# 8channelsULN2803.net
KiCad netlist of a schematic drawn in EAGLE
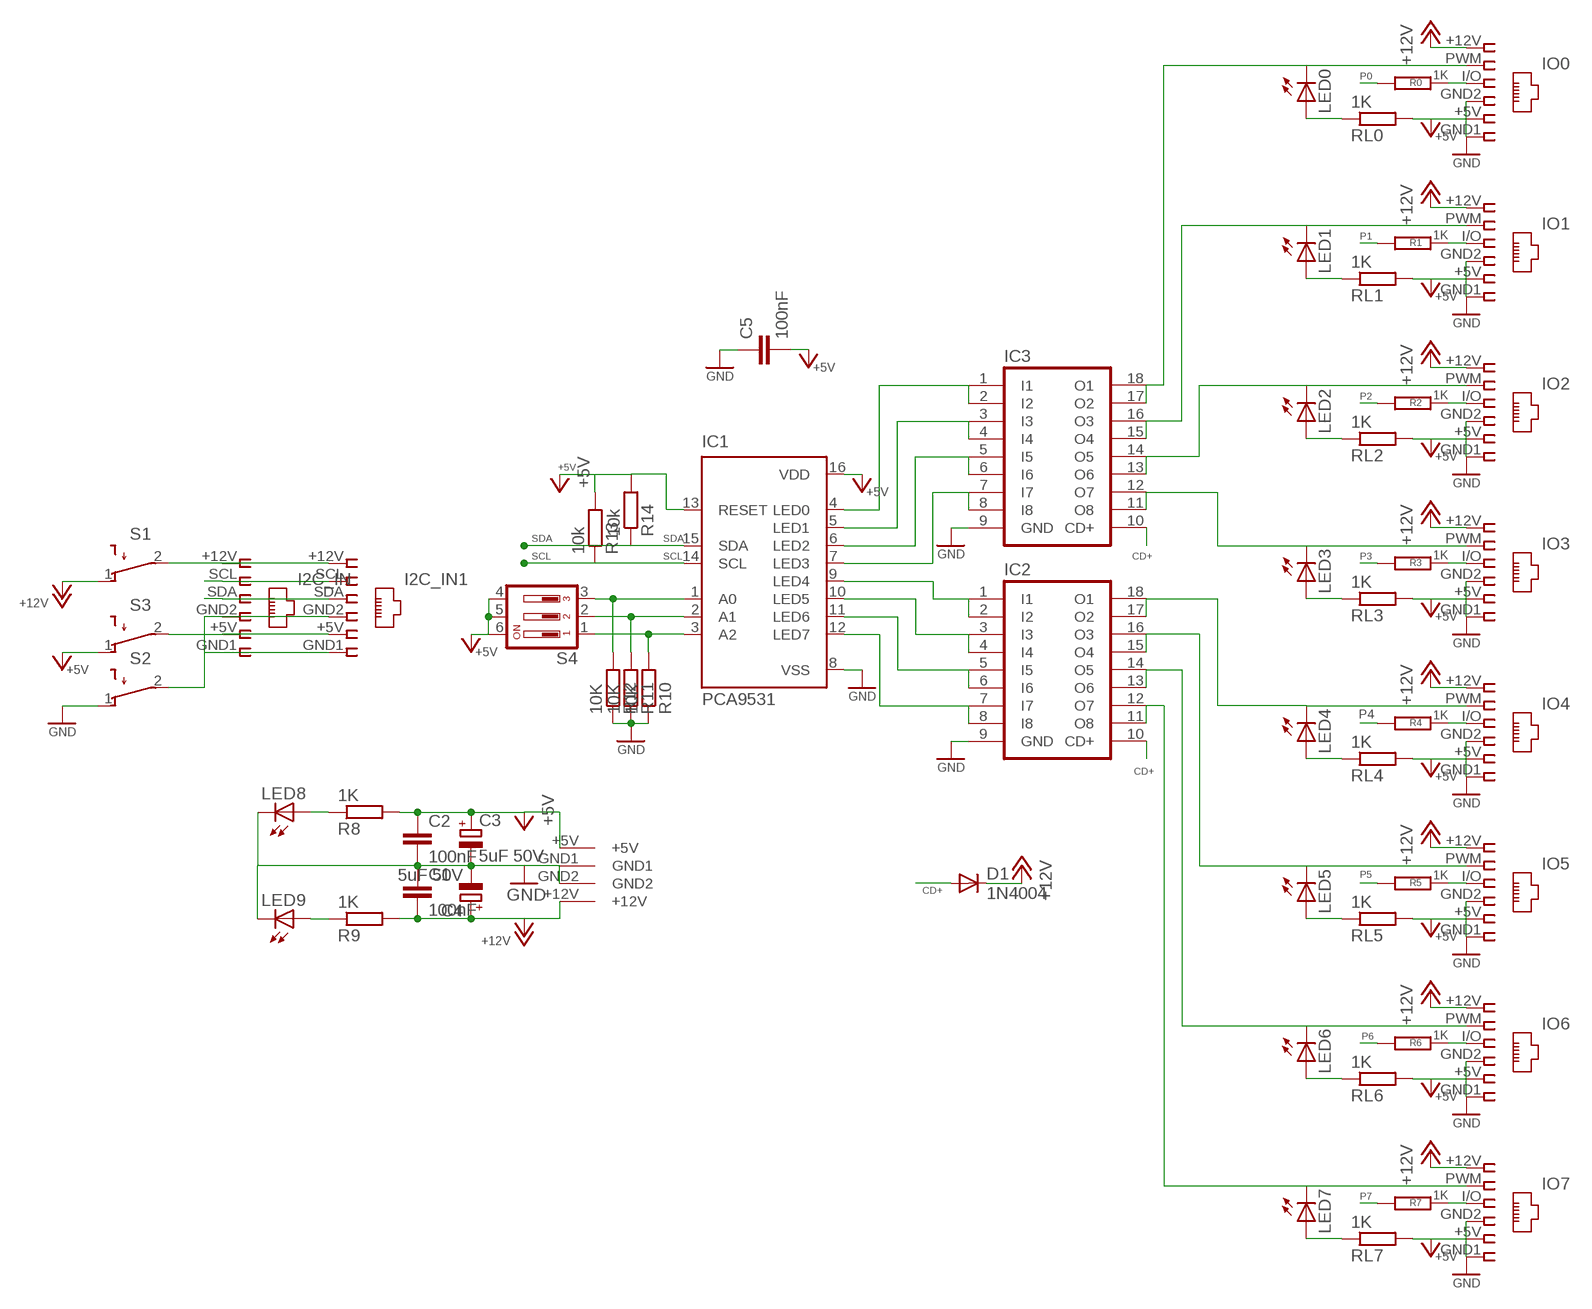
[diagram p0: schematic, sheet 1]

(export (version "E")
  (design (tool "Eeschema 10.0.6"))
  (components
    (comp (ref "C1")
      (value "100nF")
      (footprint "eagle-import:C1206")
      (libsource (lib "eagle-import") (part "C-EUC1206"))
    )
    (comp (ref "C2")
      (value "100nF")
      (footprint "eagle-import:C1206")
      (libsource (lib "eagle-import") (part "C-EUC1206"))
    )
    (comp (ref "C3")
      (value "5uF 50V")
      (footprint "eagle-import:E3,5-8")
      (libsource (lib "eagle-import") (part "CPOL-EUE3.5-8"))
    )
    (comp (ref "C4")
      (value "5uF 50V")
      (footprint "eagle-import:E3,5-8")
      (libsource (lib "eagle-import") (part "CPOL-EUE3.5-8"))
    )
    (comp (ref "C5")
      (value "100nF")
      (footprint "eagle-import:C1206")
      (libsource (lib "eagle-import") (part "C-EUC1206"))
    )
    (comp (ref "D1")
      (value "1N4004")
      (footprint "eagle-import:DO41-10")
      (libsource (lib "eagle-import") (part "1N4004"))
    )
    (comp (ref "I2C_IN")
      (value "I2C 1")
      (footprint "eagle-import:RJ12-STRAIGHT-I2C")
      (libsource (lib "eagle-import") (part "RJ12STRAIGHT-I2C"))
    )
    (comp (ref "I2C_IN1")
      (value "I2C 2")
      (footprint "eagle-import:RJ12-STRAIGHT-I2C")
      (libsource (lib "eagle-import") (part "RJ12STRAIGHT-I2C"))
    )
    (comp (ref "IC1")
      (value "PCA9531")
      (footprint "eagle-import:SO16")
      (libsource (lib "eagle-import") (part "PCA9531"))
    )
    (comp (ref "IC2")
      (value "ULN2803A")
      (footprint "eagle-import:DIL18")
      (libsource (lib "eagle-import") (part "ULN2803A"))
    )
    (comp (ref "IC3")
      (value "ULN2803A")
      (footprint "eagle-import:DIL18")
      (libsource (lib "eagle-import") (part "ULN2803A"))
    )
    (comp (ref "IO0")
      (value "IO0")
      (footprint "eagle-import:RJ12-STRAIGHT")
      (libsource (lib "eagle-import") (part "RJ12STRAIGHT"))
    )
    (comp (ref "IO1")
      (value "IO1")
      (footprint "eagle-import:RJ12-STRAIGHT")
      (libsource (lib "eagle-import") (part "RJ12STRAIGHT"))
    )
    (comp (ref "IO2")
      (value "IO2")
      (footprint "eagle-import:RJ12-STRAIGHT")
      (libsource (lib "eagle-import") (part "RJ12STRAIGHT"))
    )
    (comp (ref "IO3")
      (value "IO3")
      (footprint "eagle-import:RJ12-STRAIGHT")
      (libsource (lib "eagle-import") (part "RJ12STRAIGHT"))
    )
    (comp (ref "IO4")
      (value "IO4")
      (footprint "eagle-import:RJ12-STRAIGHT")
      (libsource (lib "eagle-import") (part "RJ12STRAIGHT"))
    )
    (comp (ref "IO5")
      (value "IO5")
      (footprint "eagle-import:RJ12-STRAIGHT")
      (libsource (lib "eagle-import") (part "RJ12STRAIGHT"))
    )
    (comp (ref "IO6")
      (value "IO6")
      (footprint "eagle-import:RJ12-STRAIGHT")
      (libsource (lib "eagle-import") (part "RJ12STRAIGHT"))
    )
    (comp (ref "IO7")
      (value "IO7")
      (footprint "eagle-import:RJ12-STRAIGHT")
      (libsource (lib "eagle-import") (part "RJ12STRAIGHT"))
    )
    (comp (ref "LED0")
      (value "LED3MM")
      (footprint "eagle-import:LED3MM")
      (libsource (lib "eagle-import") (part "LED3MM"))
    )
    (comp (ref "LED1")
      (value "LED3MM")
      (footprint "eagle-import:LED3MM")
      (libsource (lib "eagle-import") (part "LED3MM"))
    )
    (comp (ref "LED2")
      (value "LED3MM")
      (footprint "eagle-import:LED3MM")
      (libsource (lib "eagle-import") (part "LED3MM"))
    )
    (comp (ref "LED3")
      (value "LED3MM")
      (footprint "eagle-import:LED3MM")
      (libsource (lib "eagle-import") (part "LED3MM"))
    )
    (comp (ref "LED4")
      (value "LED3MM")
      (footprint "eagle-import:LED3MM")
      (libsource (lib "eagle-import") (part "LED3MM"))
    )
    (comp (ref "LED5")
      (value "LED3MM")
      (footprint "eagle-import:LED3MM")
      (libsource (lib "eagle-import") (part "LED3MM"))
    )
    (comp (ref "LED6")
      (value "LED3MM")
      (footprint "eagle-import:LED3MM")
      (libsource (lib "eagle-import") (part "LED3MM"))
    )
    (comp (ref "LED7")
      (value "LED3MM")
      (footprint "eagle-import:LED3MM")
      (libsource (lib "eagle-import") (part "LED3MM"))
    )
    (comp (ref "LED8")
      (value "LED3MM")
      (footprint "eagle-import:LED3MM")
      (libsource (lib "eagle-import") (part "LED3MM"))
    )
    (comp (ref "LED9")
      (value "LED3MM")
      (footprint "eagle-import:LED3MM")
      (libsource (lib "eagle-import") (part "LED3MM"))
    )
    (comp (ref "R0")
      (value "1K")
      (footprint "eagle-import:M1206")
      (libsource (lib "eagle-import") (part "R-EU_M1206"))
    )
    (comp (ref "R1")
      (value "1K")
      (footprint "eagle-import:M1206")
      (libsource (lib "eagle-import") (part "R-EU_M1206"))
    )
    (comp (ref "R2")
      (value "1K")
      (footprint "eagle-import:M1206")
      (libsource (lib "eagle-import") (part "R-EU_M1206"))
    )
    (comp (ref "R3")
      (value "1K")
      (footprint "eagle-import:M1206")
      (libsource (lib "eagle-import") (part "R-EU_M1206"))
    )
    (comp (ref "R4")
      (value "1K")
      (footprint "eagle-import:M1206")
      (libsource (lib "eagle-import") (part "R-EU_M1206"))
    )
    (comp (ref "R5")
      (value "1K")
      (footprint "eagle-import:M1206")
      (libsource (lib "eagle-import") (part "R-EU_M1206"))
    )
    (comp (ref "R6")
      (value "1K")
      (footprint "eagle-import:M1206")
      (libsource (lib "eagle-import") (part "R-EU_M1206"))
    )
    (comp (ref "R7")
      (value "1K")
      (footprint "eagle-import:M1206")
      (libsource (lib "eagle-import") (part "R-EU_M1206"))
    )
    (comp (ref "R8")
      (value "1K")
      (footprint "eagle-import:M1206")
      (libsource (lib "eagle-import") (part "R-EU_M1206"))
    )
    (comp (ref "R9")
      (value "1K")
      (footprint "eagle-import:M1206")
      (libsource (lib "eagle-import") (part "R-EU_M1206"))
    )
    (comp (ref "R10")
      (value "10K")
      (footprint "eagle-import:M1206")
      (libsource (lib "eagle-import") (part "R-EU_M1206"))
    )
    (comp (ref "R11")
      (value "10K")
      (footprint "eagle-import:M1206")
      (libsource (lib "eagle-import") (part "R-EU_M1206"))
    )
    (comp (ref "R12")
      (value "10K")
      (footprint "eagle-import:M1206")
      (libsource (lib "eagle-import") (part "R-EU_M1206"))
    )
    (comp (ref "R13")
      (value "10k")
      (footprint "eagle-import:M1206")
      (libsource (lib "eagle-import") (part "R-EU_M1206"))
    )
    (comp (ref "R14")
      (value "10k")
      (footprint "eagle-import:M1206")
      (libsource (lib "eagle-import") (part "R-EU_M1206"))
    )
    (comp (ref "RL0")
      (value "1K")
      (footprint "eagle-import:M1206")
      (libsource (lib "eagle-import") (part "R-EU_M1206"))
    )
    (comp (ref "RL1")
      (value "1K")
      (footprint "eagle-import:M1206")
      (libsource (lib "eagle-import") (part "R-EU_M1206"))
    )
    (comp (ref "RL2")
      (value "1K")
      (footprint "eagle-import:M1206")
      (libsource (lib "eagle-import") (part "R-EU_M1206"))
    )
    (comp (ref "RL3")
      (value "1K")
      (footprint "eagle-import:M1206")
      (libsource (lib "eagle-import") (part "R-EU_M1206"))
    )
    (comp (ref "RL4")
      (value "1K")
      (footprint "eagle-import:M1206")
      (libsource (lib "eagle-import") (part "R-EU_M1206"))
    )
    (comp (ref "RL5")
      (value "1K")
      (footprint "eagle-import:M1206")
      (libsource (lib "eagle-import") (part "R-EU_M1206"))
    )
    (comp (ref "RL6")
      (value "1K")
      (footprint "eagle-import:M1206")
      (libsource (lib "eagle-import") (part "R-EU_M1206"))
    )
    (comp (ref "RL7")
      (value "1K")
      (footprint "eagle-import:M1206")
      (libsource (lib "eagle-import") (part "R-EU_M1206"))
    )
    (comp (ref "S1")
      (value "SWITCHSWITCH")
      (footprint "eagle-import:SWITCH2")
      (libsource (lib "eagle-import") (part "SWITCHSWITCH"))
    )
    (comp (ref "S2")
      (value "SWITCHPAD")
      (footprint "eagle-import:PADS2")
      (libsource (lib "eagle-import") (part "SWITCHPAD"))
    )
    (comp (ref "S3")
      (value "SWITCHSWITCH")
      (footprint "eagle-import:SWITCH2")
      (libsource (lib "eagle-import") (part "SWITCHSWITCH"))
    )
    (comp (ref "S4")
      (value "DIP03YL")
      (footprint "eagle-import:DIP03YL")
      (libsource (lib "eagle-import") (part "DIP03YL"))
    )
    (comp (ref "U$2")
      (value "KPJX-4S-S")
      (footprint "eagle-import:KPJX-4S-S")
      (libsource (lib "eagle-import") (part "KPJX-4S-S"))
    )
  )
  (nets
    (net (code "1") (name "+5V") (class "Default")
      (node (ref "C2") (pin "1") (pinfunction "1_1") (pintype "passive"))
      (node (ref "C3") (pin "+") (pinfunction "+_+") (pintype "passive"))
      (node (ref "C5") (pin "2") (pinfunction "2_2") (pintype "passive"))
      (node (ref "IC1") (pin "13") (pinfunction "RESET_13") (pintype "input"))
      (node (ref "IC1") (pin "16") (pinfunction "VDD_16") (pintype "power_in"))
      (node (ref "IO0") (pin "+5V") (pinfunction "5_+5V") (pintype "power_in"))
      (node (ref "IO1") (pin "+5V") (pinfunction "5_+5V") (pintype "power_in"))
      (node (ref "IO2") (pin "+5V") (pinfunction "5_+5V") (pintype "power_in"))
      (node (ref "IO3") (pin "+5V") (pinfunction "5_+5V") (pintype "power_in"))
      (node (ref "IO4") (pin "+5V") (pinfunction "5_+5V") (pintype "power_in"))
      (node (ref "IO5") (pin "+5V") (pinfunction "5_+5V") (pintype "power_in"))
      (node (ref "IO6") (pin "+5V") (pinfunction "5_+5V") (pintype "power_in"))
      (node (ref "IO7") (pin "+5V") (pinfunction "5_+5V") (pintype "power_in"))
      (node (ref "R13") (pin "2") (pinfunction "2_2") (pintype "passive"))
      (node (ref "R14") (pin "2") (pinfunction "2_2") (pintype "passive"))
      (node (ref "R8") (pin "2") (pinfunction "2_2") (pintype "passive"))
      (node (ref "RL0") (pin "2") (pinfunction "2_2") (pintype "passive"))
      (node (ref "RL1") (pin "2") (pinfunction "2_2") (pintype "passive"))
      (node (ref "RL2") (pin "2") (pinfunction "2_2") (pintype "passive"))
      (node (ref "RL3") (pin "2") (pinfunction "2_2") (pintype "passive"))
      (node (ref "RL4") (pin "2") (pinfunction "2_2") (pintype "passive"))
      (node (ref "RL5") (pin "2") (pinfunction "2_2") (pintype "passive"))
      (node (ref "RL6") (pin "2") (pinfunction "2_2") (pintype "passive"))
      (node (ref "RL7") (pin "2") (pinfunction "2_2") (pintype "passive"))
      (node (ref "S3") (pin "1") (pinfunction "O_1") (pintype "passive"))
      (node (ref "S4") (pin "4") (pinfunction "4_4") (pintype "passive"))
      (node (ref "S4") (pin "5") (pinfunction "5_5") (pintype "passive"))
      (node (ref "S4") (pin "6") (pinfunction "6_6") (pintype "passive"))
      (node (ref "U$2") (pin "+5V") (pinfunction "+5V_+5V") (pintype "power_in"))
    )
    (net (code "2") (name "+12V") (class "Default")
      (node (ref "C1") (pin "2") (pinfunction "2_2") (pintype "passive"))
      (node (ref "C4") (pin "+") (pinfunction "+_+") (pintype "passive"))
      (node (ref "D1") (pin "C") (pinfunction "C_C") (pintype "passive"))
      (node (ref "IO0") (pin "+12V") (pinfunction "1_+12V") (pintype "power_in"))
      (node (ref "IO1") (pin "+12V") (pinfunction "1_+12V") (pintype "power_in"))
      (node (ref "IO2") (pin "+12V") (pinfunction "1_+12V") (pintype "power_in"))
      (node (ref "IO3") (pin "+12V") (pinfunction "1_+12V") (pintype "power_in"))
      (node (ref "IO4") (pin "+12V") (pinfunction "1_+12V") (pintype "power_in"))
      (node (ref "IO5") (pin "+12V") (pinfunction "1_+12V") (pintype "power_in"))
      (node (ref "IO6") (pin "+12V") (pinfunction "1_+12V") (pintype "power_in"))
      (node (ref "IO7") (pin "+12V") (pinfunction "1_+12V") (pintype "power_in"))
      (node (ref "R9") (pin "2") (pinfunction "2_2") (pintype "passive"))
      (node (ref "S1") (pin "1") (pinfunction "O_1") (pintype "passive"))
      (node (ref "U$2") (pin "+12V") (pinfunction "+12V_+12V") (pintype "power_in"))
    )
    (net (code "3") (name "/CD+") (class "Default")
      (node (ref "D1") (pin "A") (pinfunction "A_A") (pintype "passive"))
      (node (ref "IC2") (pin "10") (pinfunction "CD+_10") (pintype "passive"))
      (node (ref "IC3") (pin "10") (pinfunction "CD+_10") (pintype "passive"))
    )
    (net (code "4") (name "/P0") (class "Default")
      (node (ref "IC1") (pin "4") (pinfunction "LED0_4") (pintype "bidirectional"))
      (node (ref "IC3") (pin "1") (pinfunction "I1_1") (pintype "input"))
      (node (ref "IC3") (pin "2") (pinfunction "I2_2") (pintype "input"))
      (node (ref "R0") (pin "2") (pinfunction "2_2") (pintype "passive"))
    )
    (net (code "5") (name "/P1") (class "Default")
      (node (ref "IC1") (pin "5") (pinfunction "LED1_5") (pintype "bidirectional"))
      (node (ref "IC3") (pin "3") (pinfunction "I3_3") (pintype "input"))
      (node (ref "IC3") (pin "4") (pinfunction "I4_4") (pintype "input"))
      (node (ref "R1") (pin "2") (pinfunction "2_2") (pintype "passive"))
    )
    (net (code "6") (name "/P2") (class "Default")
      (node (ref "IC1") (pin "6") (pinfunction "LED2_6") (pintype "bidirectional"))
      (node (ref "IC3") (pin "5") (pinfunction "I5_5") (pintype "input"))
      (node (ref "IC3") (pin "6") (pinfunction "I6_6") (pintype "input"))
      (node (ref "R2") (pin "2") (pinfunction "2_2") (pintype "passive"))
    )
    (net (code "7") (name "/P3") (class "Default")
      (node (ref "IC1") (pin "7") (pinfunction "LED3_7") (pintype "bidirectional"))
      (node (ref "IC3") (pin "7") (pinfunction "I7_7") (pintype "input"))
      (node (ref "IC3") (pin "8") (pinfunction "I8_8") (pintype "input"))
      (node (ref "R3") (pin "2") (pinfunction "2_2") (pintype "passive"))
    )
    (net (code "8") (name "/P4") (class "Default")
      (node (ref "IC1") (pin "9") (pinfunction "LED4_9") (pintype "bidirectional"))
      (node (ref "IC2") (pin "1") (pinfunction "I1_1") (pintype "input"))
      (node (ref "IC2") (pin "2") (pinfunction "I2_2") (pintype "input"))
      (node (ref "R4") (pin "2") (pinfunction "2_2") (pintype "passive"))
    )
    (net (code "9") (name "/P5") (class "Default")
      (node (ref "IC1") (pin "10") (pinfunction "LED5_10") (pintype "bidirectional"))
      (node (ref "IC2") (pin "3") (pinfunction "I3_3") (pintype "input"))
      (node (ref "IC2") (pin "4") (pinfunction "I4_4") (pintype "input"))
      (node (ref "R5") (pin "2") (pinfunction "2_2") (pintype "passive"))
    )
    (net (code "10") (name "/P6") (class "Default")
      (node (ref "IC1") (pin "11") (pinfunction "LED6_11") (pintype "bidirectional"))
      (node (ref "IC2") (pin "5") (pinfunction "I5_5") (pintype "input"))
      (node (ref "IC2") (pin "6") (pinfunction "I6_6") (pintype "input"))
      (node (ref "R6") (pin "2") (pinfunction "2_2") (pintype "passive"))
    )
    (net (code "11") (name "/P7") (class "Default")
      (node (ref "IC1") (pin "12") (pinfunction "LED7_12") (pintype "bidirectional"))
      (node (ref "IC2") (pin "7") (pinfunction "I7_7") (pintype "input"))
      (node (ref "IC2") (pin "8") (pinfunction "I8_8") (pintype "input"))
      (node (ref "R7") (pin "2") (pinfunction "2_2") (pintype "passive"))
    )
    (net (code "12") (name "/SCL") (class "Default")
      (node (ref "I2C_IN") (pin "SCL") (pinfunction "2_SCL") (pintype "bidirectional"))
      (node (ref "I2C_IN1") (pin "SCL") (pinfunction "2_SCL") (pintype "bidirectional"))
      (node (ref "IC1") (pin "14") (pinfunction "SCL_14") (pintype "input"))
      (node (ref "R13") (pin "1") (pinfunction "1_1") (pintype "passive"))
    )
    (net (code "13") (name "/SDA") (class "Default")
      (node (ref "I2C_IN") (pin "SDA") (pinfunction "3_SDA") (pintype "bidirectional"))
      (node (ref "I2C_IN1") (pin "SDA") (pinfunction "3_SDA") (pintype "bidirectional"))
      (node (ref "IC1") (pin "15") (pinfunction "SDA_15") (pintype "bidirectional"))
      (node (ref "R14") (pin "1") (pinfunction "1_1") (pintype "passive"))
    )
    (net (code "14") (name "GND") (class "Default")
      (node (ref "C1") (pin "1") (pinfunction "1_1") (pintype "passive"))
      (node (ref "C2") (pin "2") (pinfunction "2_2") (pintype "passive"))
      (node (ref "C3") (pin "-") (pinfunction "-_-") (pintype "passive"))
      (node (ref "C4") (pin "-") (pinfunction "-_-") (pintype "passive"))
      (node (ref "C5") (pin "1") (pinfunction "1_1") (pintype "passive"))
      (node (ref "IC1") (pin "8") (pinfunction "VSS_8") (pintype "power_in"))
      (node (ref "IC2") (pin "9") (pinfunction "GND_9") (pintype "power_in"))
      (node (ref "IC3") (pin "9") (pinfunction "GND_9") (pintype "power_in"))
      (node (ref "IO0") (pin "GND1") (pinfunction "6_GND1") (pintype "power_in"))
      (node (ref "IO0") (pin "GND2") (pinfunction "4_GND2") (pintype "power_in"))
      (node (ref "IO1") (pin "GND1") (pinfunction "6_GND1") (pintype "power_in"))
      (node (ref "IO1") (pin "GND2") (pinfunction "4_GND2") (pintype "power_in"))
      (node (ref "IO2") (pin "GND1") (pinfunction "6_GND1") (pintype "power_in"))
      (node (ref "IO2") (pin "GND2") (pinfunction "4_GND2") (pintype "power_in"))
      (node (ref "IO3") (pin "GND1") (pinfunction "6_GND1") (pintype "power_in"))
      (node (ref "IO3") (pin "GND2") (pinfunction "4_GND2") (pintype "power_in"))
      (node (ref "IO4") (pin "GND1") (pinfunction "6_GND1") (pintype "power_in"))
      (node (ref "IO4") (pin "GND2") (pinfunction "4_GND2") (pintype "power_in"))
      (node (ref "IO5") (pin "GND1") (pinfunction "6_GND1") (pintype "power_in"))
      (node (ref "IO5") (pin "GND2") (pinfunction "4_GND2") (pintype "power_in"))
      (node (ref "IO6") (pin "GND1") (pinfunction "6_GND1") (pintype "power_in"))
      (node (ref "IO6") (pin "GND2") (pinfunction "4_GND2") (pintype "power_in"))
      (node (ref "IO7") (pin "GND1") (pinfunction "6_GND1") (pintype "power_in"))
      (node (ref "IO7") (pin "GND2") (pinfunction "4_GND2") (pintype "power_in"))
      (node (ref "LED8") (pin "K") (pinfunction "C_K") (pintype "passive"))
      (node (ref "LED9") (pin "K") (pinfunction "C_K") (pintype "passive"))
      (node (ref "R10") (pin "1") (pinfunction "1_1") (pintype "passive"))
      (node (ref "R11") (pin "1") (pinfunction "1_1") (pintype "passive"))
      (node (ref "R12") (pin "1") (pinfunction "1_1") (pintype "passive"))
      (node (ref "S2") (pin "1") (pinfunction "O_1") (pintype "passive"))
      (node (ref "U$2") (pin "GND1") (pinfunction "GND1_GND1") (pintype "input"))
      (node (ref "U$2") (pin "GND2") (pinfunction "GND2_GND2") (pintype "input"))
    )
    (net (code "15") (name "Net-(I2C_IN-1)") (class "Default")
      (node (ref "I2C_IN") (pin "+12V") (pinfunction "1_+12V") (pintype "power_in"))
      (node (ref "I2C_IN1") (pin "+12V") (pinfunction "1_+12V") (pintype "power_in"))
      (node (ref "S1") (pin "2") (pinfunction "P_2") (pintype "passive"))
    )
    (net (code "16") (name "Net-(I2C_IN-4)") (class "Default")
      (node (ref "I2C_IN") (pin "GND1") (pinfunction "6_GND1") (pintype "power_in"))
      (node (ref "I2C_IN") (pin "GND2") (pinfunction "4_GND2") (pintype "power_in"))
      (node (ref "I2C_IN1") (pin "GND1") (pinfunction "6_GND1") (pintype "power_in"))
      (node (ref "I2C_IN1") (pin "GND2") (pinfunction "4_GND2") (pintype "power_in"))
      (node (ref "S2") (pin "2") (pinfunction "P_2") (pintype "passive"))
    )
    (net (code "17") (name "Net-(I2C_IN-5)") (class "Default")
      (node (ref "I2C_IN") (pin "+5V") (pinfunction "5_+5V") (pintype "power_in"))
      (node (ref "I2C_IN1") (pin "+5V") (pinfunction "5_+5V") (pintype "power_in"))
      (node (ref "S3") (pin "2") (pinfunction "P_2") (pintype "passive"))
    )
    (net (code "18") (name "Net-(IC1-A0)") (class "Default")
      (node (ref "IC1") (pin "1") (pinfunction "A0_1") (pintype "input"))
      (node (ref "R12") (pin "2") (pinfunction "2_2") (pintype "passive"))
      (node (ref "S4") (pin "3") (pinfunction "3_3") (pintype "passive"))
    )
    (net (code "19") (name "Net-(IC1-A1)") (class "Default")
      (node (ref "IC1") (pin "2") (pinfunction "A1_2") (pintype "input"))
      (node (ref "R11") (pin "2") (pinfunction "2_2") (pintype "passive"))
      (node (ref "S4") (pin "2") (pinfunction "2_2") (pintype "passive"))
    )
    (net (code "20") (name "Net-(IC1-A2)") (class "Default")
      (node (ref "IC1") (pin "3") (pinfunction "A2_3") (pintype "input"))
      (node (ref "R10") (pin "2") (pinfunction "2_2") (pintype "passive"))
      (node (ref "S4") (pin "1") (pinfunction "1_1") (pintype "passive"))
    )
    (net (code "21") (name "Net-(IC2-O1)") (class "Default")
      (node (ref "IC2") (pin "17") (pinfunction "O2_17") (pintype "open_collector"))
      (node (ref "IC2") (pin "18") (pinfunction "O1_18") (pintype "open_collector"))
      (node (ref "IO4") (pin "PWM") (pinfunction "2_PWM") (pintype "bidirectional"))
      (node (ref "LED4") (pin "K") (pinfunction "C_K") (pintype "passive"))
    )
    (net (code "22") (name "Net-(IC2-O3)") (class "Default")
      (node (ref "IC2") (pin "15") (pinfunction "O4_15") (pintype "open_collector"))
      (node (ref "IC2") (pin "16") (pinfunction "O3_16") (pintype "open_collector"))
      (node (ref "IO5") (pin "PWM") (pinfunction "2_PWM") (pintype "bidirectional"))
      (node (ref "LED5") (pin "K") (pinfunction "C_K") (pintype "passive"))
    )
    (net (code "23") (name "Net-(IC2-O5)") (class "Default")
      (node (ref "IC2") (pin "13") (pinfunction "O6_13") (pintype "open_collector"))
      (node (ref "IC2") (pin "14") (pinfunction "O5_14") (pintype "open_collector"))
      (node (ref "IO6") (pin "PWM") (pinfunction "2_PWM") (pintype "bidirectional"))
      (node (ref "LED6") (pin "K") (pinfunction "C_K") (pintype "passive"))
    )
    (net (code "24") (name "Net-(IC2-O7)") (class "Default")
      (node (ref "IC2") (pin "11") (pinfunction "O8_11") (pintype "open_collector"))
      (node (ref "IC2") (pin "12") (pinfunction "O7_12") (pintype "open_collector"))
      (node (ref "IO7") (pin "PWM") (pinfunction "2_PWM") (pintype "bidirectional"))
      (node (ref "LED7") (pin "K") (pinfunction "C_K") (pintype "passive"))
    )
    (net (code "25") (name "Net-(IC3-O1)") (class "Default")
      (node (ref "IC3") (pin "17") (pinfunction "O2_17") (pintype "open_collector"))
      (node (ref "IC3") (pin "18") (pinfunction "O1_18") (pintype "open_collector"))
      (node (ref "IO0") (pin "PWM") (pinfunction "2_PWM") (pintype "bidirectional"))
      (node (ref "LED0") (pin "K") (pinfunction "C_K") (pintype "passive"))
    )
    (net (code "26") (name "Net-(IC3-O3)") (class "Default")
      (node (ref "IC3") (pin "15") (pinfunction "O4_15") (pintype "open_collector"))
      (node (ref "IC3") (pin "16") (pinfunction "O3_16") (pintype "open_collector"))
      (node (ref "IO1") (pin "PWM") (pinfunction "2_PWM") (pintype "bidirectional"))
      (node (ref "LED1") (pin "K") (pinfunction "C_K") (pintype "passive"))
    )
    (net (code "27") (name "Net-(IC3-O5)") (class "Default")
      (node (ref "IC3") (pin "13") (pinfunction "O6_13") (pintype "open_collector"))
      (node (ref "IC3") (pin "14") (pinfunction "O5_14") (pintype "open_collector"))
      (node (ref "IO2") (pin "PWM") (pinfunction "2_PWM") (pintype "bidirectional"))
      (node (ref "LED2") (pin "K") (pinfunction "C_K") (pintype "passive"))
    )
    (net (code "28") (name "Net-(IC3-O7)") (class "Default")
      (node (ref "IC3") (pin "11") (pinfunction "O8_11") (pintype "open_collector"))
      (node (ref "IC3") (pin "12") (pinfunction "O7_12") (pintype "open_collector"))
      (node (ref "IO3") (pin "PWM") (pinfunction "2_PWM") (pintype "bidirectional"))
      (node (ref "LED3") (pin "K") (pinfunction "C_K") (pintype "passive"))
    )
    (net (code "29") (name "Net-(IO0-3)") (class "Default")
      (node (ref "IO0") (pin "I/O") (pinfunction "3_I/O") (pintype "bidirectional"))
      (node (ref "R0") (pin "1") (pinfunction "1_1") (pintype "passive"))
    )
    (net (code "30") (name "Net-(IO1-3)") (class "Default")
      (node (ref "IO1") (pin "I/O") (pinfunction "3_I/O") (pintype "bidirectional"))
      (node (ref "R1") (pin "1") (pinfunction "1_1") (pintype "passive"))
    )
    (net (code "31") (name "Net-(IO2-3)") (class "Default")
      (node (ref "IO2") (pin "I/O") (pinfunction "3_I/O") (pintype "bidirectional"))
      (node (ref "R2") (pin "1") (pinfunction "1_1") (pintype "passive"))
    )
    (net (code "32") (name "Net-(IO3-3)") (class "Default")
      (node (ref "IO3") (pin "I/O") (pinfunction "3_I/O") (pintype "bidirectional"))
      (node (ref "R3") (pin "1") (pinfunction "1_1") (pintype "passive"))
    )
    (net (code "33") (name "Net-(IO4-3)") (class "Default")
      (node (ref "IO4") (pin "I/O") (pinfunction "3_I/O") (pintype "bidirectional"))
      (node (ref "R4") (pin "1") (pinfunction "1_1") (pintype "passive"))
    )
    (net (code "34") (name "Net-(IO5-3)") (class "Default")
      (node (ref "IO5") (pin "I/O") (pinfunction "3_I/O") (pintype "bidirectional"))
      (node (ref "R5") (pin "1") (pinfunction "1_1") (pintype "passive"))
    )
    (net (code "35") (name "Net-(IO6-3)") (class "Default")
      (node (ref "IO6") (pin "I/O") (pinfunction "3_I/O") (pintype "bidirectional"))
      (node (ref "R6") (pin "1") (pinfunction "1_1") (pintype "passive"))
    )
    (net (code "36") (name "Net-(IO7-3)") (class "Default")
      (node (ref "IO7") (pin "I/O") (pinfunction "3_I/O") (pintype "bidirectional"))
      (node (ref "R7") (pin "1") (pinfunction "1_1") (pintype "passive"))
    )
    (net (code "37") (name "Net-(LED0-PadA)") (class "Default")
      (node (ref "LED0") (pin "A") (pinfunction "A_A") (pintype "passive"))
      (node (ref "RL0") (pin "1") (pinfunction "1_1") (pintype "passive"))
    )
    (net (code "38") (name "Net-(LED1-PadA)") (class "Default")
      (node (ref "LED1") (pin "A") (pinfunction "A_A") (pintype "passive"))
      (node (ref "RL1") (pin "1") (pinfunction "1_1") (pintype "passive"))
    )
    (net (code "39") (name "Net-(LED2-PadA)") (class "Default")
      (node (ref "LED2") (pin "A") (pinfunction "A_A") (pintype "passive"))
      (node (ref "RL2") (pin "1") (pinfunction "1_1") (pintype "passive"))
    )
    (net (code "40") (name "Net-(LED3-PadA)") (class "Default")
      (node (ref "LED3") (pin "A") (pinfunction "A_A") (pintype "passive"))
      (node (ref "RL3") (pin "1") (pinfunction "1_1") (pintype "passive"))
    )
    (net (code "41") (name "Net-(LED4-PadA)") (class "Default")
      (node (ref "LED4") (pin "A") (pinfunction "A_A") (pintype "passive"))
      (node (ref "RL4") (pin "1") (pinfunction "1_1") (pintype "passive"))
    )
    (net (code "42") (name "Net-(LED5-PadA)") (class "Default")
      (node (ref "LED5") (pin "A") (pinfunction "A_A") (pintype "passive"))
      (node (ref "RL5") (pin "1") (pinfunction "1_1") (pintype "passive"))
    )
    (net (code "43") (name "Net-(LED6-PadA)") (class "Default")
      (node (ref "LED6") (pin "A") (pinfunction "A_A") (pintype "passive"))
      (node (ref "RL6") (pin "1") (pinfunction "1_1") (pintype "passive"))
    )
    (net (code "44") (name "Net-(LED7-PadA)") (class "Default")
      (node (ref "LED7") (pin "A") (pinfunction "A_A") (pintype "passive"))
      (node (ref "RL7") (pin "1") (pinfunction "1_1") (pintype "passive"))
    )
    (net (code "45") (name "Net-(LED8-PadA)") (class "Default")
      (node (ref "LED8") (pin "A") (pinfunction "A_A") (pintype "passive"))
      (node (ref "R8") (pin "1") (pinfunction "1_1") (pintype "passive"))
    )
    (net (code "46") (name "Net-(LED9-PadA)") (class "Default")
      (node (ref "LED9") (pin "A") (pinfunction "A_A") (pintype "passive"))
      (node (ref "R9") (pin "1") (pinfunction "1_1") (pintype "passive"))
    )
  )
)
